# fpga_flash_debug.net
KiCad netlist of a schematic drawn in Altium Designer
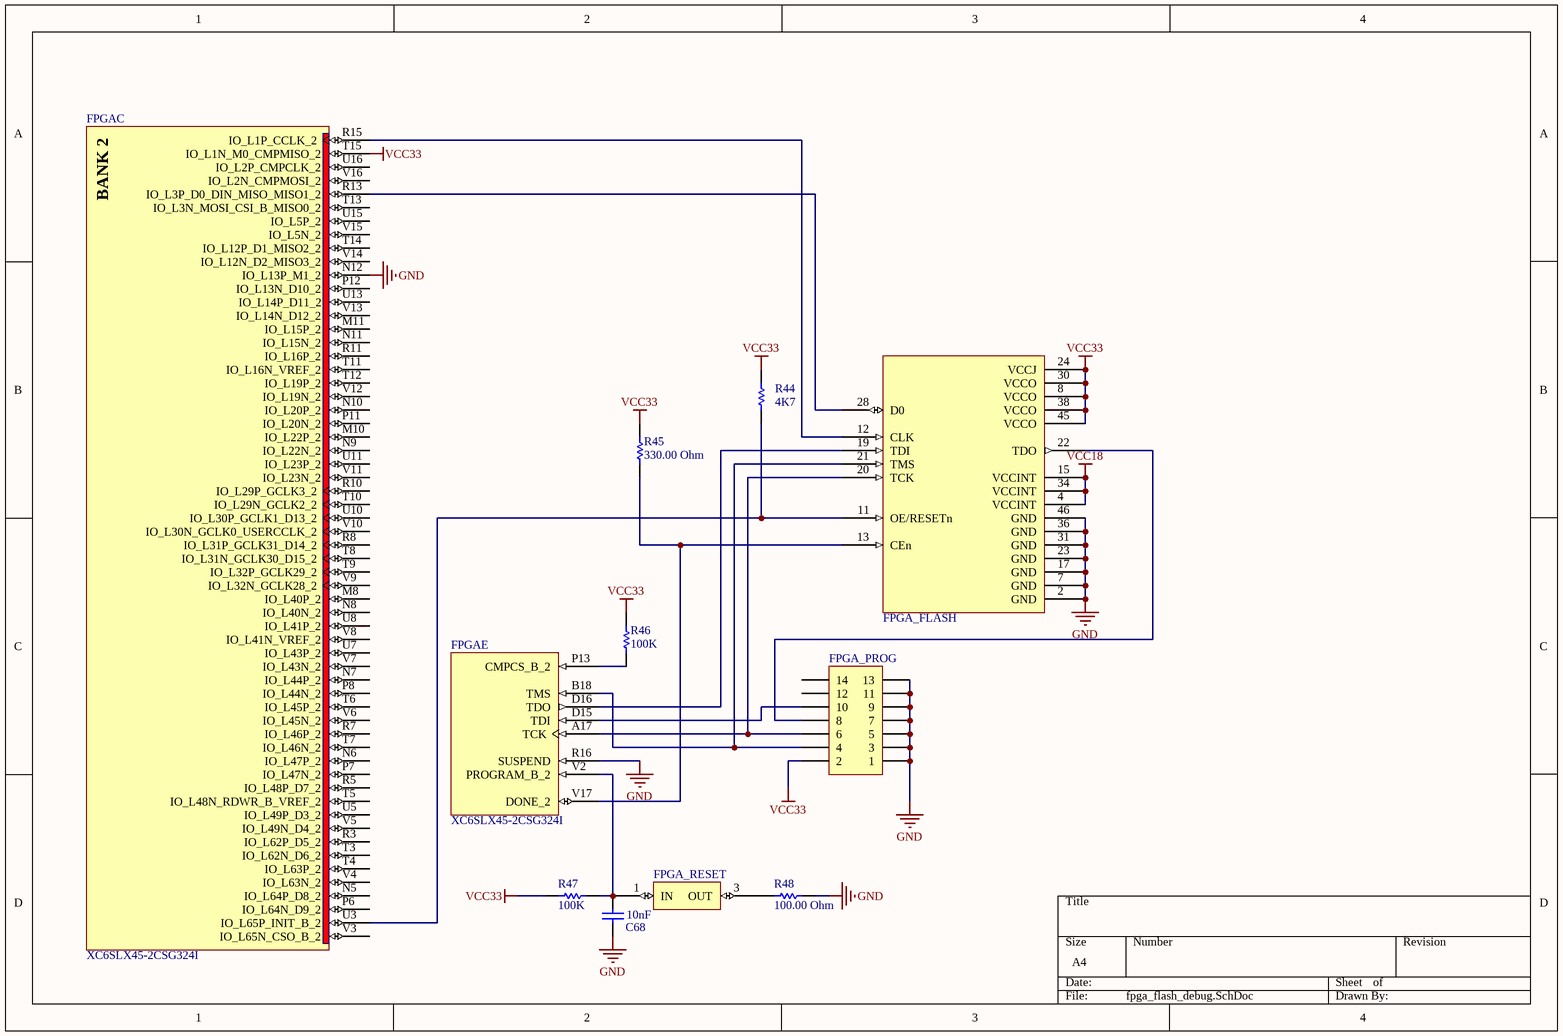
[diagram p0: fpga_flash_debug.SchDoc]

(export (version "E")
  (design (tool "Eeschema 10.0.6"))
  (components
    (comp (ref "C68")
      (value "10nF")
      (footprint "CAPC0805(2012)75_N")
      (description "CAP 10nF 50V ±10% 0805 (2012 Metric) Thickness 0.75mm SMD")
      (fields (field (name "TOLERANCE") "±10%"))
      (libsource (lib "Altium Content Vault") (part "CMP-1036-03842-1"))
    )
    (comp (ref "FPGA")
      (value "XC6SLX45-2CSG324I")
      (footprint "CSG324")
      (libsource (lib "") (part "XC6SLX45-2CSG324I_1"))
    )
    (comp (ref "FPGA_FLASH")
      (value "XCF16PVOG48C")
      (footprint "FPGA_FLASH")
      (libsource (lib "XCF16PVOG48C") (part "XCF16PVOG48C"))
    )
    (comp (ref "FPGA_PROG")
      (value "Header 7X2")
      (footprint "HDR2X7")
      (description "Header, 7-Pin, Dual row")
      (fields (field (name "PUBLISHER") "Altium Limited"))
      (libsource (lib "Miscellaneous Connectors") (part "Header 7X2"))
    )
    (comp (ref "FPGA_RESET")
      (value "BUTTON")
      (footprint "BUTTON")
      (libsource (lib "PowerConnector") (part "BUTTON"))
    )
    (comp (ref "R44")
      (value "4K7")
      (footprint "RESC0805(2012)_M")
      (description "4K7 0.125W 1% 0805 (2012 Metric)  SMD")
      (fields (field (name "POWER") "0.125 W") (field (name "TOLERANCE") "1 %"))
      (libsource (lib "Altium Content Vault") (part "CMP-1013-00586-1"))
    )
    (comp (ref "R45")
      (value "330.00 Ohm")
      (footprint "RESC0805(2012)_M")
      (description "330R 0.125W 1% 0805 (2012 Metric)  SMD")
      (fields (field (name "POWER") "0.125 W") (field (name "TOLERANCE") "1 %"))
      (libsource (lib "Altium Content Vault") (part "CMP-1013-00454-1"))
    )
    (comp (ref "R46")
      (value "100K")
      (footprint "RESC0805(2012)_L")
      (description "100K 0.125W 5% 0805 (2012 Metric)  SMD")
      (fields (field (name "TOLERANCE") "5 %") (field (name "POWER") "0.125 W"))
      (libsource (lib "Altium Content Vault") (part "CMP-1013-00122-1"))
    )
    (comp (ref "R47")
      (value "100K")
      (footprint "RESC0805(2012)_L")
      (description "100K 0.125W 5% 0805 (2012 Metric)  SMD")
      (fields (field (name "TOLERANCE") "5 %") (field (name "POWER") "0.125 W"))
      (libsource (lib "Altium Content Vault") (part "CMP-1013-00122-1"))
    )
    (comp (ref "R48")
      (value "100.00 Ohm")
      (footprint "RESC0805(2012)_M")
      (description "100R 0.125W 5% 0805 (2012 Metric)  SMD")
      (fields (field (name "TOLERANCE") "5 %") (field (name "POWER") "0.125 W"))
      (libsource (lib "Altium Content Vault") (part "CMP-1013-00050-1"))
    )
  )
  (nets
    (net (code "1") (name "GND") (class "Default")
      (node (ref "C68") (pin "1") (pinfunction "1_1") (pintype "passive"))
      (node (ref "FPGA") (pin "N12") (pinfunction "IO_L13P_M1_2_N12") (pintype "bidirectional"))
      (node (ref "FPGA") (pin "R16") (pinfunction "SUSPEND_R16") (pintype "input"))
      (node (ref "FPGA_FLASH") (pin "17") (pinfunction "GND_17") (pintype "power_in"))
      (node (ref "FPGA_FLASH") (pin "2") (pinfunction "GND_2") (pintype "power_in"))
      (node (ref "FPGA_FLASH") (pin "23") (pinfunction "GND_23") (pintype "power_in"))
      (node (ref "FPGA_FLASH") (pin "31") (pinfunction "GND_31") (pintype "power_in"))
      (node (ref "FPGA_FLASH") (pin "36") (pinfunction "GND_36") (pintype "power_in"))
      (node (ref "FPGA_FLASH") (pin "46") (pinfunction "GND_46") (pintype "power_in"))
      (node (ref "FPGA_FLASH") (pin "7") (pinfunction "GND_7") (pintype "power_in"))
      (node (ref "FPGA_PROG") (pin "1") (pinfunction "1_1") (pintype "passive"))
      (node (ref "FPGA_PROG") (pin "11") (pinfunction "11_11") (pintype "passive"))
      (node (ref "FPGA_PROG") (pin "13") (pinfunction "13_13") (pintype "passive"))
      (node (ref "FPGA_PROG") (pin "3") (pinfunction "3_3") (pintype "passive"))
      (node (ref "FPGA_PROG") (pin "5") (pinfunction "5_5") (pintype "passive"))
      (node (ref "FPGA_PROG") (pin "7") (pinfunction "7_7") (pintype "passive"))
      (node (ref "FPGA_PROG") (pin "9") (pinfunction "9_9") (pintype "passive"))
      (node (ref "R48") (pin "2") (pinfunction "2_2") (pintype "passive"))
    )
    (net (code "2") (name "Net-(FPGAC-IO_L1P_CCLK_2)") (class "Default")
      (node (ref "FPGA") (pin "R15") (pinfunction "IO_L1P_CCLK_2_R15") (pintype "bidirectional"))
      (node (ref "FPGA_FLASH") (pin "12") (pinfunction "CLK_12") (pintype "input"))
    )
    (net (code "3") (name "Net-(FPGAC-IO_L3P_D0_DIN_MISO_MISO1_2)") (class "Default")
      (node (ref "FPGA") (pin "R13") (pinfunction "IO_L3P_D0_DIN_MISO_MISO1_2_R13") (pintype "bidirectional"))
      (node (ref "FPGA_FLASH") (pin "28") (pinfunction "D0_28") (pintype "bidirectional"))
    )
    (net (code "4") (name "Net-(FPGAC-IO_L65P_INIT_B_2)") (class "Default")
      (node (ref "FPGA") (pin "U3") (pinfunction "IO_L65P_INIT_B_2_U3") (pintype "bidirectional"))
      (node (ref "FPGA_FLASH") (pin "11") (pinfunction "OE/RESETn_11") (pintype "input"))
      (node (ref "R44") (pin "2") (pinfunction "2_2") (pintype "passive"))
    )
    (net (code "5") (name "Net-(FPGAE-CMPCS_B_2)") (class "Default")
      (node (ref "FPGA") (pin "P13") (pinfunction "CMPCS_B_2_P13") (pintype "input"))
      (node (ref "R46") (pin "1") (pinfunction "1_1") (pintype "passive"))
    )
    (net (code "6") (name "Net-(FPGAE-DONE_2)") (class "Default")
      (node (ref "FPGA") (pin "V17") (pinfunction "DONE_2_V17") (pintype "bidirectional"))
      (node (ref "FPGA_FLASH") (pin "13") (pinfunction "CEn_13") (pintype "input"))
      (node (ref "R45") (pin "2") (pinfunction "2_2") (pintype "passive"))
    )
    (net (code "7") (name "Net-(FPGAE-PROGRAM_B_2)") (class "Default")
      (node (ref "C68") (pin "2") (pinfunction "2_2") (pintype "passive"))
      (node (ref "FPGA") (pin "V2") (pinfunction "PROGRAM_B_2_V2") (pintype "input"))
      (node (ref "FPGA_RESET") (pin "1") (pinfunction "IN_1") (pintype "bidirectional"))
      (node (ref "R47") (pin "1") (pinfunction "1_1") (pintype "passive"))
    )
    (net (code "8") (name "Net-(FPGAE-TCK)") (class "Default")
      (node (ref "FPGA") (pin "A17") (pinfunction "TCK_A17") (pintype "input"))
      (node (ref "FPGA_FLASH") (pin "20") (pinfunction "TCK_20") (pintype "input"))
      (node (ref "FPGA_PROG") (pin "6") (pinfunction "6_6") (pintype "passive"))
    )
    (net (code "9") (name "Net-(FPGAE-TDI)") (class "Default")
      (node (ref "FPGA") (pin "D15") (pinfunction "TDI_D15") (pintype "input"))
      (node (ref "FPGA_PROG") (pin "10") (pinfunction "10_10") (pintype "passive"))
    )
    (net (code "10") (name "Net-(FPGAE-TDO)") (class "Default")
      (node (ref "FPGA") (pin "D16") (pinfunction "TDO_D16") (pintype "output"))
      (node (ref "FPGA_FLASH") (pin "19") (pinfunction "TDI_19") (pintype "input"))
    )
    (net (code "11") (name "Net-(FPGAE-TMS)") (class "Default")
      (node (ref "FPGA") (pin "B18") (pinfunction "TMS_B18") (pintype "input"))
      (node (ref "FPGA_FLASH") (pin "21") (pinfunction "TMS_21") (pintype "input"))
      (node (ref "FPGA_PROG") (pin "4") (pinfunction "4_4") (pintype "passive"))
    )
    (net (code "12") (name "Net-(FPGA_FLASH-TDO)") (class "Default")
      (node (ref "FPGA_FLASH") (pin "22") (pinfunction "TDO_22") (pintype "output"))
      (node (ref "FPGA_PROG") (pin "8") (pinfunction "8_8") (pintype "passive"))
    )
    (net (code "13") (name "Net-(FPGA_RESET-OUT)") (class "Default")
      (node (ref "FPGA_RESET") (pin "3") (pinfunction "OUT_3") (pintype "bidirectional"))
      (node (ref "R48") (pin "1") (pinfunction "1_1") (pintype "passive"))
    )
    (net (code "14") (name "VCC18") (class "Default")
      (node (ref "FPGA_FLASH") (pin "15") (pinfunction "VCCINT_15") (pintype "power_in"))
      (node (ref "FPGA_FLASH") (pin "34") (pinfunction "VCCINT_34") (pintype "power_in"))
      (node (ref "FPGA_FLASH") (pin "4") (pinfunction "VCCINT_4") (pintype "power_in"))
    )
    (net (code "15") (name "VCC33") (class "Default")
      (node (ref "FPGA") (pin "T15") (pinfunction "IO_L1N_M0_CMPMISO_2_T15") (pintype "bidirectional"))
      (node (ref "FPGA_FLASH") (pin "24") (pinfunction "VCCJ_24") (pintype "power_in"))
      (node (ref "FPGA_FLASH") (pin "30") (pinfunction "VCCO_30") (pintype "power_in"))
      (node (ref "FPGA_FLASH") (pin "38") (pinfunction "VCCO_38") (pintype "power_in"))
      (node (ref "FPGA_FLASH") (pin "45") (pinfunction "VCCO_45") (pintype "power_in"))
      (node (ref "FPGA_FLASH") (pin "8") (pinfunction "VCCO_8") (pintype "power_in"))
      (node (ref "FPGA_PROG") (pin "2") (pinfunction "2_2") (pintype "passive"))
      (node (ref "R44") (pin "1") (pinfunction "1_1") (pintype "passive"))
      (node (ref "R45") (pin "1") (pinfunction "1_1") (pintype "passive"))
      (node (ref "R46") (pin "2") (pinfunction "2_2") (pintype "passive"))
      (node (ref "R47") (pin "2") (pinfunction "2_2") (pintype "passive"))
    )
    (net (code "16") (name "unconnected-(FPGAC-IO_L2N_CMPMOSI_2-PadV16)") (class "Default")
      (node (ref "FPGA") (pin "V16") (pinfunction "IO_L2N_CMPMOSI_2_V16") (pintype "bidirectional"))
    )
    (net (code "17") (name "unconnected-(FPGAC-IO_L2P_CMPCLK_2-PadU16)") (class "Default")
      (node (ref "FPGA") (pin "U16") (pinfunction "IO_L2P_CMPCLK_2_U16") (pintype "bidirectional"))
    )
    (net (code "18") (name "unconnected-(FPGAC-IO_L3N_MOSI_CSI_B_MISO0_2-PadT13)") (class "Default")
      (node (ref "FPGA") (pin "T13") (pinfunction "IO_L3N_MOSI_CSI_B_MISO0_2_T13") (pintype "bidirectional"))
    )
    (net (code "19") (name "unconnected-(FPGAC-IO_L5N_2-PadV15)") (class "Default")
      (node (ref "FPGA") (pin "V15") (pinfunction "IO_L5N_2_V15") (pintype "bidirectional"))
    )
    (net (code "20") (name "unconnected-(FPGAC-IO_L5P_2-PadU15)") (class "Default")
      (node (ref "FPGA") (pin "U15") (pinfunction "IO_L5P_2_U15") (pintype "bidirectional"))
    )
    (net (code "21") (name "unconnected-(FPGAC-IO_L12N_D2_MISO3_2-PadV14)") (class "Default")
      (node (ref "FPGA") (pin "V14") (pinfunction "IO_L12N_D2_MISO3_2_V14") (pintype "bidirectional"))
    )
    (net (code "22") (name "unconnected-(FPGAC-IO_L12P_D1_MISO2_2-PadT14)") (class "Default")
      (node (ref "FPGA") (pin "T14") (pinfunction "IO_L12P_D1_MISO2_2_T14") (pintype "bidirectional"))
    )
    (net (code "23") (name "unconnected-(FPGAC-IO_L13N_D10_2-PadP12)") (class "Default")
      (node (ref "FPGA") (pin "P12") (pinfunction "IO_L13N_D10_2_P12") (pintype "bidirectional"))
    )
    (net (code "24") (name "unconnected-(FPGAC-IO_L14N_D12_2-PadV13)") (class "Default")
      (node (ref "FPGA") (pin "V13") (pinfunction "IO_L14N_D12_2_V13") (pintype "bidirectional"))
    )
    (net (code "25") (name "unconnected-(FPGAC-IO_L14P_D11_2-PadU13)") (class "Default")
      (node (ref "FPGA") (pin "U13") (pinfunction "IO_L14P_D11_2_U13") (pintype "bidirectional"))
    )
    (net (code "26") (name "unconnected-(FPGAC-IO_L15N_2-PadN11)") (class "Default")
      (node (ref "FPGA") (pin "N11") (pinfunction "IO_L15N_2_N11") (pintype "bidirectional"))
    )
    (net (code "27") (name "unconnected-(FPGAC-IO_L15P_2-PadM11)") (class "Default")
      (node (ref "FPGA") (pin "M11") (pinfunction "IO_L15P_2_M11") (pintype "bidirectional"))
    )
    (net (code "28") (name "unconnected-(FPGAC-IO_L16N_VREF_2-PadT11)") (class "Default")
      (node (ref "FPGA") (pin "T11") (pinfunction "IO_L16N_VREF_2_T11") (pintype "bidirectional"))
    )
    (net (code "29") (name "unconnected-(FPGAC-IO_L16P_2-PadR11)") (class "Default")
      (node (ref "FPGA") (pin "R11") (pinfunction "IO_L16P_2_R11") (pintype "bidirectional"))
    )
    (net (code "30") (name "unconnected-(FPGAC-IO_L19N_2-PadV12)") (class "Default")
      (node (ref "FPGA") (pin "V12") (pinfunction "IO_L19N_2_V12") (pintype "bidirectional"))
    )
    (net (code "31") (name "unconnected-(FPGAC-IO_L19P_2-PadT12)") (class "Default")
      (node (ref "FPGA") (pin "T12") (pinfunction "IO_L19P_2_T12") (pintype "bidirectional"))
    )
    (net (code "32") (name "unconnected-(FPGAC-IO_L20N_2-PadP11)") (class "Default")
      (node (ref "FPGA") (pin "P11") (pinfunction "IO_L20N_2_P11") (pintype "bidirectional"))
    )
    (net (code "33") (name "unconnected-(FPGAC-IO_L20P_2-PadN10)") (class "Default")
      (node (ref "FPGA") (pin "N10") (pinfunction "IO_L20P_2_N10") (pintype "bidirectional"))
    )
    (net (code "34") (name "unconnected-(FPGAC-IO_L22N_2-PadN9)") (class "Default")
      (node (ref "FPGA") (pin "N9") (pinfunction "IO_L22N_2_N9") (pintype "bidirectional"))
    )
    (net (code "35") (name "unconnected-(FPGAC-IO_L22P_2-PadM10)") (class "Default")
      (node (ref "FPGA") (pin "M10") (pinfunction "IO_L22P_2_M10") (pintype "bidirectional"))
    )
    (net (code "36") (name "unconnected-(FPGAC-IO_L23N_2-PadV11)") (class "Default")
      (node (ref "FPGA") (pin "V11") (pinfunction "IO_L23N_2_V11") (pintype "bidirectional"))
    )
    (net (code "37") (name "unconnected-(FPGAC-IO_L23P_2-PadU11)") (class "Default")
      (node (ref "FPGA") (pin "U11") (pinfunction "IO_L23P_2_U11") (pintype "bidirectional"))
    )
    (net (code "38") (name "unconnected-(FPGAC-IO_L29N_GCLK2_2-PadT10)") (class "Default")
      (node (ref "FPGA") (pin "T10") (pinfunction "IO_L29N_GCLK2_2_T10") (pintype "bidirectional"))
    )
    (net (code "39") (name "unconnected-(FPGAC-IO_L29P_GCLK3_2-PadR10)") (class "Default")
      (node (ref "FPGA") (pin "R10") (pinfunction "IO_L29P_GCLK3_2_R10") (pintype "bidirectional"))
    )
    (net (code "40") (name "unconnected-(FPGAC-IO_L30N_GCLK0_USERCCLK_2-PadV10)") (class "Default")
      (node (ref "FPGA") (pin "V10") (pinfunction "IO_L30N_GCLK0_USERCCLK_2_V10") (pintype "bidirectional"))
    )
    (net (code "41") (name "unconnected-(FPGAC-IO_L30P_GCLK1_D13_2-PadU10)") (class "Default")
      (node (ref "FPGA") (pin "U10") (pinfunction "IO_L30P_GCLK1_D13_2_U10") (pintype "bidirectional"))
    )
    (net (code "42") (name "unconnected-(FPGAC-IO_L31N_GCLK30_D15_2-PadT8)") (class "Default")
      (node (ref "FPGA") (pin "T8") (pinfunction "IO_L31N_GCLK30_D15_2_T8") (pintype "bidirectional"))
    )
    (net (code "43") (name "unconnected-(FPGAC-IO_L31P_GCLK31_D14_2-PadR8)") (class "Default")
      (node (ref "FPGA") (pin "R8") (pinfunction "IO_L31P_GCLK31_D14_2_R8") (pintype "bidirectional"))
    )
    (net (code "44") (name "unconnected-(FPGAC-IO_L32N_GCLK28_2-PadV9)") (class "Default")
      (node (ref "FPGA") (pin "V9") (pinfunction "IO_L32N_GCLK28_2_V9") (pintype "bidirectional"))
    )
    (net (code "45") (name "unconnected-(FPGAC-IO_L32P_GCLK29_2-PadT9)") (class "Default")
      (node (ref "FPGA") (pin "T9") (pinfunction "IO_L32P_GCLK29_2_T9") (pintype "bidirectional"))
    )
    (net (code "46") (name "unconnected-(FPGAC-IO_L40N_2-PadN8)") (class "Default")
      (node (ref "FPGA") (pin "N8") (pinfunction "IO_L40N_2_N8") (pintype "bidirectional"))
    )
    (net (code "47") (name "unconnected-(FPGAC-IO_L40P_2-PadM8)") (class "Default")
      (node (ref "FPGA") (pin "M8") (pinfunction "IO_L40P_2_M8") (pintype "bidirectional"))
    )
    (net (code "48") (name "unconnected-(FPGAC-IO_L41N_VREF_2-PadV8)") (class "Default")
      (node (ref "FPGA") (pin "V8") (pinfunction "IO_L41N_VREF_2_V8") (pintype "bidirectional"))
    )
    (net (code "49") (name "unconnected-(FPGAC-IO_L41P_2-PadU8)") (class "Default")
      (node (ref "FPGA") (pin "U8") (pinfunction "IO_L41P_2_U8") (pintype "bidirectional"))
    )
    (net (code "50") (name "unconnected-(FPGAC-IO_L43N_2-PadV7)") (class "Default")
      (node (ref "FPGA") (pin "V7") (pinfunction "IO_L43N_2_V7") (pintype "bidirectional"))
    )
    (net (code "51") (name "unconnected-(FPGAC-IO_L43P_2-PadU7)") (class "Default")
      (node (ref "FPGA") (pin "U7") (pinfunction "IO_L43P_2_U7") (pintype "bidirectional"))
    )
    (net (code "52") (name "unconnected-(FPGAC-IO_L44N_2-PadP8)") (class "Default")
      (node (ref "FPGA") (pin "P8") (pinfunction "IO_L44N_2_P8") (pintype "bidirectional"))
    )
    (net (code "53") (name "unconnected-(FPGAC-IO_L44P_2-PadN7)") (class "Default")
      (node (ref "FPGA") (pin "N7") (pinfunction "IO_L44P_2_N7") (pintype "bidirectional"))
    )
    (net (code "54") (name "unconnected-(FPGAC-IO_L45N_2-PadV6)") (class "Default")
      (node (ref "FPGA") (pin "V6") (pinfunction "IO_L45N_2_V6") (pintype "bidirectional"))
    )
    (net (code "55") (name "unconnected-(FPGAC-IO_L45P_2-PadT6)") (class "Default")
      (node (ref "FPGA") (pin "T6") (pinfunction "IO_L45P_2_T6") (pintype "bidirectional"))
    )
    (net (code "56") (name "unconnected-(FPGAC-IO_L46N_2-PadT7)") (class "Default")
      (node (ref "FPGA") (pin "T7") (pinfunction "IO_L46N_2_T7") (pintype "bidirectional"))
    )
    (net (code "57") (name "unconnected-(FPGAC-IO_L46P_2-PadR7)") (class "Default")
      (node (ref "FPGA") (pin "R7") (pinfunction "IO_L46P_2_R7") (pintype "bidirectional"))
    )
    (net (code "58") (name "unconnected-(FPGAC-IO_L47N_2-PadP7)") (class "Default")
      (node (ref "FPGA") (pin "P7") (pinfunction "IO_L47N_2_P7") (pintype "bidirectional"))
    )
    (net (code "59") (name "unconnected-(FPGAC-IO_L47P_2-PadN6)") (class "Default")
      (node (ref "FPGA") (pin "N6") (pinfunction "IO_L47P_2_N6") (pintype "bidirectional"))
    )
    (net (code "60") (name "unconnected-(FPGAC-IO_L48N_RDWR_B_VREF_2-PadT5)") (class "Default")
      (node (ref "FPGA") (pin "T5") (pinfunction "IO_L48N_RDWR_B_VREF_2_T5") (pintype "bidirectional"))
    )
    (net (code "61") (name "unconnected-(FPGAC-IO_L48P_D7_2-PadR5)") (class "Default")
      (node (ref "FPGA") (pin "R5") (pinfunction "IO_L48P_D7_2_R5") (pintype "bidirectional"))
    )
    (net (code "62") (name "unconnected-(FPGAC-IO_L49N_D4_2-PadV5)") (class "Default")
      (node (ref "FPGA") (pin "V5") (pinfunction "IO_L49N_D4_2_V5") (pintype "bidirectional"))
    )
    (net (code "63") (name "unconnected-(FPGAC-IO_L49P_D3_2-PadU5)") (class "Default")
      (node (ref "FPGA") (pin "U5") (pinfunction "IO_L49P_D3_2_U5") (pintype "bidirectional"))
    )
    (net (code "64") (name "unconnected-(FPGAC-IO_L62N_D6_2-PadT3)") (class "Default")
      (node (ref "FPGA") (pin "T3") (pinfunction "IO_L62N_D6_2_T3") (pintype "bidirectional"))
    )
    (net (code "65") (name "unconnected-(FPGAC-IO_L62P_D5_2-PadR3)") (class "Default")
      (node (ref "FPGA") (pin "R3") (pinfunction "IO_L62P_D5_2_R3") (pintype "bidirectional"))
    )
    (net (code "66") (name "unconnected-(FPGAC-IO_L63N_2-PadV4)") (class "Default")
      (node (ref "FPGA") (pin "V4") (pinfunction "IO_L63N_2_V4") (pintype "bidirectional"))
    )
    (net (code "67") (name "unconnected-(FPGAC-IO_L63P_2-PadT4)") (class "Default")
      (node (ref "FPGA") (pin "T4") (pinfunction "IO_L63P_2_T4") (pintype "bidirectional"))
    )
    (net (code "68") (name "unconnected-(FPGAC-IO_L64N_D9_2-PadP6)") (class "Default")
      (node (ref "FPGA") (pin "P6") (pinfunction "IO_L64N_D9_2_P6") (pintype "bidirectional"))
    )
    (net (code "69") (name "unconnected-(FPGAC-IO_L64P_D8_2-PadN5)") (class "Default")
      (node (ref "FPGA") (pin "N5") (pinfunction "IO_L64P_D8_2_N5") (pintype "bidirectional"))
    )
    (net (code "70") (name "unconnected-(FPGAC-IO_L65N_CSO_B_2-PadV3)") (class "Default")
      (node (ref "FPGA") (pin "V3") (pinfunction "IO_L65N_CSO_B_2_V3") (pintype "bidirectional"))
    )
    (net (code "71") (name "unconnected-(FPGA_PROG-Pad12)") (class "Default")
      (node (ref "FPGA_PROG") (pin "12") (pinfunction "12_12") (pintype "passive"))
    )
    (net (code "72") (name "unconnected-(FPGA_PROG-Pad14)") (class "Default")
      (node (ref "FPGA_PROG") (pin "14") (pinfunction "14_14") (pintype "passive"))
    )
  )
)
